# LightSensorCircuitSMT.net
KiCad netlist of a schematic drawn in EAGLE
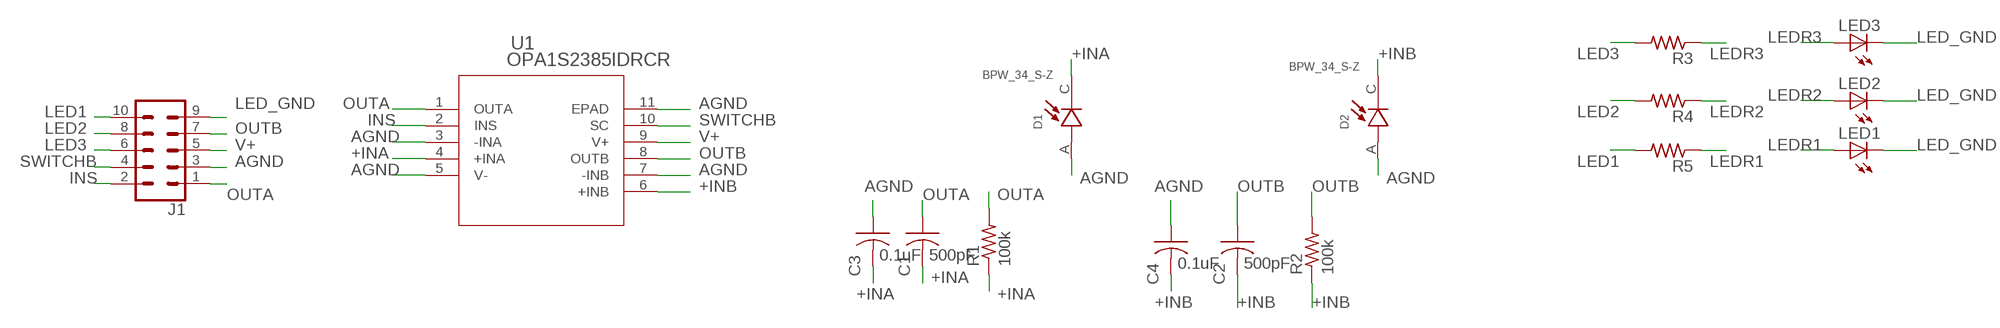
[diagram p0: schematic, sheet 1]

(export (version "E")
  (design (tool "Eeschema 10.0.6"))
  (components
    (comp (ref "C1")
      (value "500pF")
      (footprint "eagle-import:C0603")
      (libsource (lib "eagle-import") (part "C-USC0603"))
    )
    (comp (ref "C2")
      (value "500pF")
      (footprint "eagle-import:C0603")
      (libsource (lib "eagle-import") (part "C-USC0603"))
    )
    (comp (ref "C3")
      (value "0.1uF")
      (footprint "eagle-import:C0603")
      (libsource (lib "eagle-import") (part "C-USC0603"))
    )
    (comp (ref "C4")
      (value "0.1uF")
      (footprint "eagle-import:C0603")
      (libsource (lib "eagle-import") (part "C-USC0603"))
    )
    (comp (ref "D1")
      (value "BPW_34_S-Z")
      (footprint "eagle-import:DIO_BPW_34_S-Z")
      (fields (field (name "MF") "OSRAM Opto") (field (name "MP") "BPW 34 S-Z"))
      (libsource (lib "eagle-import") (part "BPW_34_S-Z"))
    )
    (comp (ref "D2")
      (value "BPW_34_S-Z")
      (footprint "eagle-import:DIO_BPW_34_S-Z")
      (fields (field (name "MF") "OSRAM Opto") (field (name "MP") "BPW 34 S-Z"))
      (libsource (lib "eagle-import") (part "BPW_34_S-Z"))
    )
    (comp (ref "J1")
      (value "CONN_05X2NO_SILK")
      (footprint "eagle-import:2X5_NOSILK")
      (libsource (lib "eagle-import") (part "CONN_05X2NO_SILK"))
    )
    (comp (ref "LED1")
      (value "LEDCHIPLED_1206")
      (footprint "eagle-import:CHIPLED_1206")
      (libsource (lib "eagle-import") (part "LEDCHIPLED_1206"))
    )
    (comp (ref "LED2")
      (value "LEDCHIPLED_1206")
      (footprint "eagle-import:CHIPLED_1206")
      (libsource (lib "eagle-import") (part "LEDCHIPLED_1206"))
    )
    (comp (ref "LED3")
      (value "LEDCHIPLED_1206")
      (footprint "eagle-import:CHIPLED_1206")
      (libsource (lib "eagle-import") (part "LEDCHIPLED_1206"))
    )
    (comp (ref "R1")
      (value "100k")
      (footprint "eagle-import:R0603")
      (libsource (lib "eagle-import") (part "R-US_R0603"))
    )
    (comp (ref "R2")
      (value "100k")
      (footprint "eagle-import:R0603")
      (libsource (lib "eagle-import") (part "R-US_R0603"))
    )
    (comp (ref "R3")
      (value "R-US_R0603")
      (footprint "eagle-import:R0603")
      (libsource (lib "eagle-import") (part "R-US_R0603"))
    )
    (comp (ref "R4")
      (value "R-US_R0603")
      (footprint "eagle-import:R0603")
      (libsource (lib "eagle-import") (part "R-US_R0603"))
    )
    (comp (ref "R5")
      (value "R-US_R0603")
      (footprint "eagle-import:R0603")
      (libsource (lib "eagle-import") (part "R-US_R0603"))
    )
    (comp (ref "U1")
      (value "OPA1S2385IDRCR")
      (footprint "eagle-import:DRC10_1P65X2P40_TEX")
      (fields (field (name "COPYRIGHT") "Copyright (C) 2022 Ultra Librarian. All rights reserved."))
      (libsource (lib "eagle-import") (part "OPA1S2385IDRCR"))
    )
  )
  (nets
    (net (code "1") (name "/+INA") (class "Default")
      (node (ref "C1") (pin "2") (pinfunction "2_2") (pintype "passive"))
      (node (ref "C3") (pin "2") (pinfunction "2_2") (pintype "passive"))
      (node (ref "D1") (pin "C") (pinfunction "C_C") (pintype "passive"))
      (node (ref "R1") (pin "1") (pinfunction "1_1") (pintype "passive"))
      (node (ref "U1") (pin "4") (pinfunction "+INA_4") (pintype "input"))
    )
    (net (code "2") (name "/+INB") (class "Default")
      (node (ref "C2") (pin "2") (pinfunction "2_2") (pintype "passive"))
      (node (ref "C4") (pin "2") (pinfunction "2_2") (pintype "passive"))
      (node (ref "D2") (pin "C") (pinfunction "C_C") (pintype "passive"))
      (node (ref "R2") (pin "1") (pinfunction "1_1") (pintype "passive"))
      (node (ref "U1") (pin "6") (pinfunction "+INB_6") (pintype "input"))
    )
    (net (code "3") (name "/AGND") (class "Default")
      (node (ref "C3") (pin "1") (pinfunction "1_1") (pintype "passive"))
      (node (ref "C4") (pin "1") (pinfunction "1_1") (pintype "passive"))
      (node (ref "D1") (pin "A") (pinfunction "A_A") (pintype "passive"))
      (node (ref "D2") (pin "A") (pinfunction "A_A") (pintype "passive"))
      (node (ref "J1") (pin "3") (pinfunction "3_3") (pintype "passive"))
      (node (ref "U1") (pin "11") (pinfunction "EPAD_11") (pintype "passive"))
      (node (ref "U1") (pin "3") (pinfunction "-INA_3") (pintype "input"))
      (node (ref "U1") (pin "5") (pinfunction "V-_5") (pintype "power_in"))
      (node (ref "U1") (pin "7") (pinfunction "-INB_7") (pintype "input"))
    )
    (net (code "4") (name "/INS") (class "Default")
      (node (ref "J1") (pin "2") (pinfunction "2_2") (pintype "passive"))
      (node (ref "U1") (pin "2") (pinfunction "INS_2") (pintype "input"))
    )
    (net (code "5") (name "/LED1") (class "Default")
      (node (ref "J1") (pin "10") (pinfunction "10_10") (pintype "passive"))
      (node (ref "R5") (pin "2") (pinfunction "2_2") (pintype "passive"))
    )
    (net (code "6") (name "/LED2") (class "Default")
      (node (ref "J1") (pin "8") (pinfunction "8_8") (pintype "passive"))
      (node (ref "R4") (pin "2") (pinfunction "2_2") (pintype "passive"))
    )
    (net (code "7") (name "/LED3") (class "Default")
      (node (ref "J1") (pin "6") (pinfunction "6_6") (pintype "passive"))
      (node (ref "R3") (pin "2") (pinfunction "2_2") (pintype "passive"))
    )
    (net (code "8") (name "/LEDR1") (class "Default")
      (node (ref "LED1") (pin "A") (pinfunction "A_A") (pintype "passive"))
      (node (ref "R5") (pin "1") (pinfunction "1_1") (pintype "passive"))
    )
    (net (code "9") (name "/LEDR2") (class "Default")
      (node (ref "LED2") (pin "A") (pinfunction "A_A") (pintype "passive"))
      (node (ref "R4") (pin "1") (pinfunction "1_1") (pintype "passive"))
    )
    (net (code "10") (name "/LEDR3") (class "Default")
      (node (ref "LED3") (pin "A") (pinfunction "A_A") (pintype "passive"))
      (node (ref "R3") (pin "1") (pinfunction "1_1") (pintype "passive"))
    )
    (net (code "11") (name "/LED_GND") (class "Default")
      (node (ref "J1") (pin "9") (pinfunction "9_9") (pintype "passive"))
      (node (ref "LED1") (pin "C") (pinfunction "C_C") (pintype "passive"))
      (node (ref "LED2") (pin "C") (pinfunction "C_C") (pintype "passive"))
      (node (ref "LED3") (pin "C") (pinfunction "C_C") (pintype "passive"))
    )
    (net (code "12") (name "/OUTA") (class "Default")
      (node (ref "C1") (pin "1") (pinfunction "1_1") (pintype "passive"))
      (node (ref "J1") (pin "1") (pinfunction "1_1") (pintype "passive"))
      (node (ref "R1") (pin "2") (pinfunction "2_2") (pintype "passive"))
      (node (ref "U1") (pin "1") (pinfunction "OUTA_1") (pintype "output"))
    )
    (net (code "13") (name "/OUTB") (class "Default")
      (node (ref "C2") (pin "1") (pinfunction "1_1") (pintype "passive"))
      (node (ref "J1") (pin "7") (pinfunction "7_7") (pintype "passive"))
      (node (ref "R2") (pin "2") (pinfunction "2_2") (pintype "passive"))
      (node (ref "U1") (pin "8") (pinfunction "OUTB_8") (pintype "output"))
    )
    (net (code "14") (name "/SWITCHB") (class "Default")
      (node (ref "J1") (pin "4") (pinfunction "4_4") (pintype "passive"))
      (node (ref "U1") (pin "10") (pinfunction "SC_10") (pintype "input"))
    )
    (net (code "15") (name "/V+") (class "Default")
      (node (ref "J1") (pin "5") (pinfunction "5_5") (pintype "passive"))
      (node (ref "U1") (pin "9") (pinfunction "V+_9") (pintype "power_in"))
    )
  )
)
